# NewBoarad.net
KiCad netlist of a schematic drawn in Altium Designer
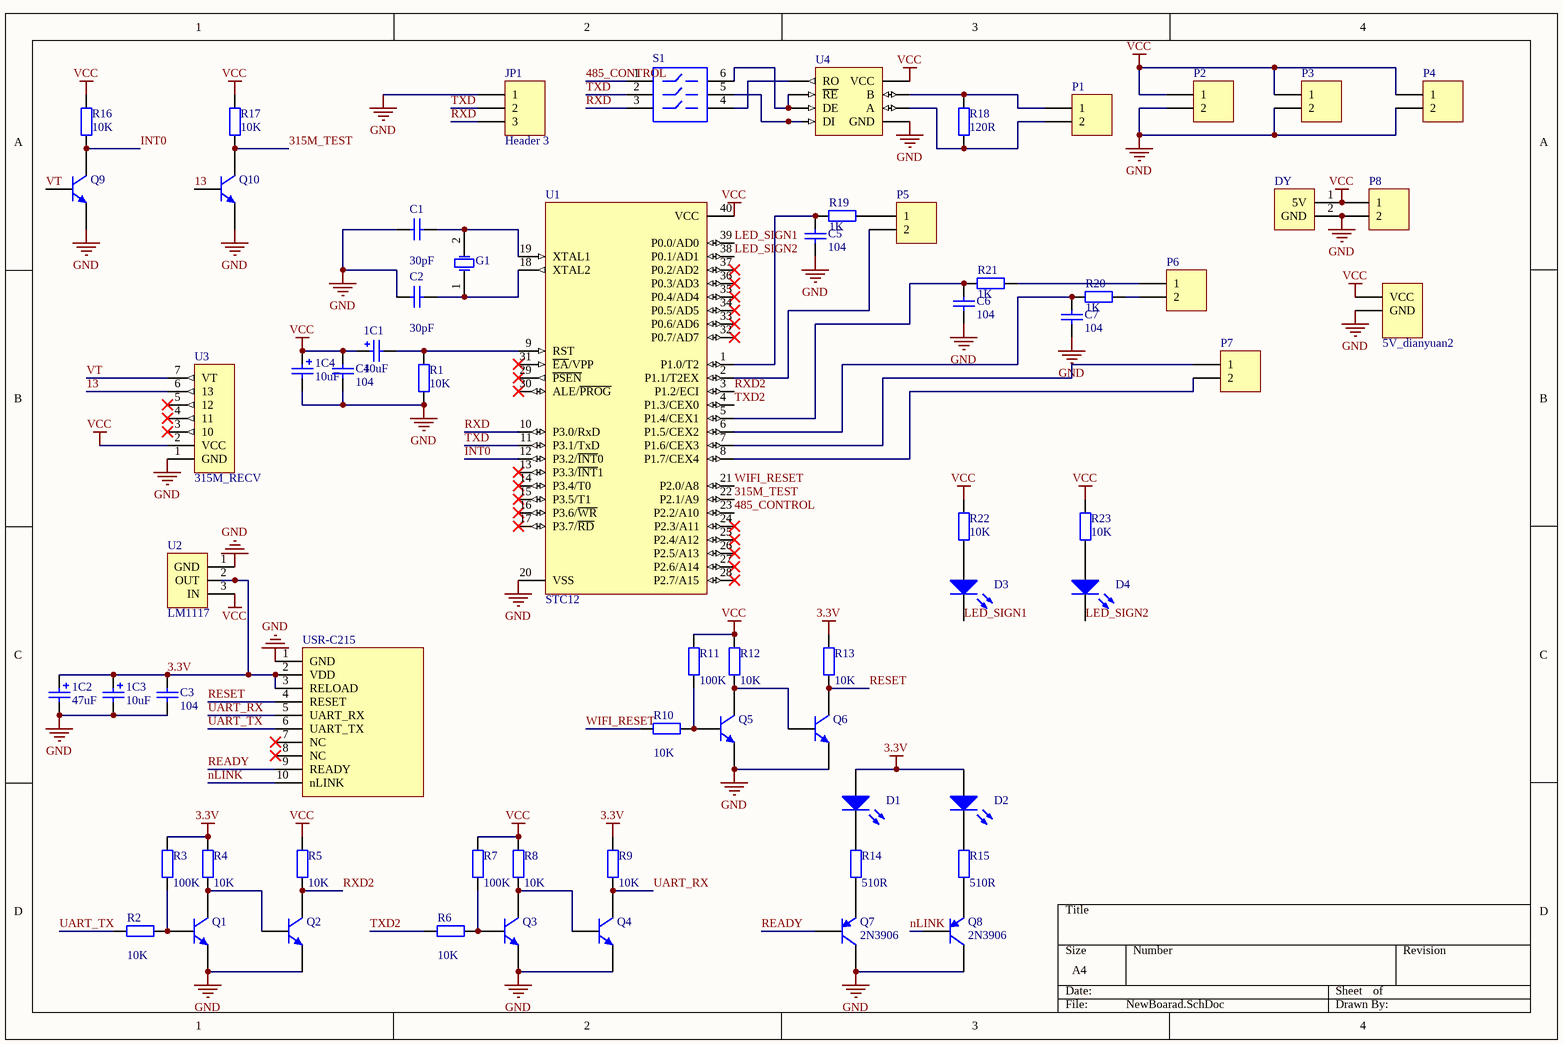
[diagram p0: NewBoarad.SchDoc]

(export (version "E")
  (design (tool "Eeschema 10.0.6"))
  (components
    (comp (ref "1C1")
      (value "10uF")
      (footprint "CAPPR5-5X5")
      (description "Polarized Capacitor (Radial)")
      (fields (field (name "Comment") "Cap Pol1") (field (name "PUBLISHER") "Altium Limited"))
      (libsource (lib "Miscellaneous Devices") (part "Cap Pol1"))
    )
    (comp (ref "1C2")
      (value "47uF")
      (footprint "CAPPR5-5X5")
      (description "Polarized Capacitor (Radial)")
      (fields (field (name "Comment") "Cap Pol1") (field (name "PUBLISHER") "Altium Limited"))
      (libsource (lib "Miscellaneous Devices") (part "Cap Pol1"))
    )
    (comp (ref "1C3")
      (value "10uF")
      (footprint "CAPPR5-5X5")
      (description "Polarized Capacitor (Radial)")
      (fields (field (name "Comment") "Cap Pol1") (field (name "PUBLISHER") "Altium Limited"))
      (libsource (lib "Miscellaneous Devices") (part "Cap Pol1"))
    )
    (comp (ref "1C4")
      (value "10uF")
      (footprint "CAPPR5-5X5")
      (description "Polarized Capacitor (Radial)")
      (fields (field (name "Comment") "Cap Pol1") (field (name "PUBLISHER") "Altium Limited"))
      (libsource (lib "Miscellaneous Devices") (part "Cap Pol1"))
    )
    (comp (ref "5V_dianyuan2")
      (value "5V_dianyuan2")
      (footprint "5v_dianyuan2")
      (libsource (lib "*") (part "5V_dianyuan2"))
    )
    (comp (ref "C1")
      (value "30pF")
      (footprint "CAPR5.08-7.8X3.2")
      (description "Capacitor")
      (fields (field (name "PUBLISHER") "Altium Limited"))
      (libsource (lib "Miscellaneous Devices") (part "Cap"))
    )
    (comp (ref "C2")
      (value "30pF")
      (footprint "CAPR5.08-7.8X3.2")
      (description "Capacitor")
      (fields (field (name "Comment") "104") (field (name "PUBLISHER") "Altium Limited"))
      (libsource (lib "Miscellaneous Devices") (part "Cap"))
    )
    (comp (ref "C3")
      (value "104")
      (footprint "CAPR5.08-7.8X3.2")
      (description "Capacitor")
      (fields (field (name "PUBLISHER") "Altium Limited"))
      (libsource (lib "Miscellaneous Devices") (part "Cap"))
    )
    (comp (ref "C4")
      (value "104")
      (footprint "CAPR5.08-7.8X3.2")
      (description "Capacitor")
      (fields (field (name "PUBLISHER") "Altium Limited"))
      (libsource (lib "Miscellaneous Devices") (part "Cap"))
    )
    (comp (ref "C5")
      (value "104")
      (footprint "CAPR5.08-7.8X3.2")
      (description "Capacitor")
      (fields (field (name "PUBLISHER") "Altium Limited"))
      (libsource (lib "Miscellaneous Devices") (part "Cap"))
    )
    (comp (ref "C6")
      (value "104")
      (footprint "CAPR5.08-7.8X3.2")
      (description "Capacitor")
      (fields (field (name "PUBLISHER") "Altium Limited"))
      (libsource (lib "Miscellaneous Devices") (part "Cap"))
    )
    (comp (ref "C7")
      (value "104")
      (footprint "CAPR5.08-7.8X3.2")
      (description "Capacitor")
      (fields (field (name "PUBLISHER") "Altium Limited"))
      (libsource (lib "Miscellaneous Devices") (part "Cap"))
    )
    (comp (ref "D1")
      (value "LED0")
      (footprint "LED-0")
      (description "Typical INFRARED GaAs LED")
      (fields (field (name "PUBLISHER") "Altium Limited"))
      (libsource (lib "*") (part "LED0"))
    )
    (comp (ref "D2")
      (value "LED0")
      (footprint "LED-0")
      (description "Typical INFRARED GaAs LED")
      (fields (field (name "PUBLISHER") "Altium Limited"))
      (libsource (lib "*") (part "LED0"))
    )
    (comp (ref "D3")
      (value "LED0")
      (footprint "LED-0")
      (description "Typical INFRARED GaAs LED")
      (fields (field (name "PUBLISHER") "Altium Limited"))
      (libsource (lib "*") (part "LED0"))
    )
    (comp (ref "D4")
      (value "LED0")
      (footprint "LED-0")
      (description "Typical INFRARED GaAs LED")
      (fields (field (name "PUBLISHER") "Altium Limited"))
      (libsource (lib "*") (part "LED0"))
    )
    (comp (ref "DY")
      (value "5V_yuankong")
      (footprint "5V_yuankong")
      (libsource (lib "HWL_1") (part "5V_yuankong"))
    )
    (comp (ref "G1")
      (value "XTAL")
      (footprint "CAPR5.08-7.8X3.2")
      (description "Crystal Oscillator")
      (fields (field (name "PUBLISHER") "Altium Limited"))
      (libsource (lib "Miscellaneous Devices") (part "XTAL"))
    )
    (comp (ref "JP1")
      (value "Header 3")
      (footprint "HDR1X3")
      (description "Header, 3-Pin")
      (fields (field (name "PUBLISHER") "Altium Limited"))
      (libsource (lib "Miscellaneous Connectors") (part "Header 3"))
    )
    (comp (ref "P1")
      (value "duanzi-2")
      (footprint "duanzi-2")
      (description "Header, 2-Pin")
      (fields (field (name "PUBLISHER") "Altium Limited"))
      (libsource (lib "*") (part "duanzi-2"))
    )
    (comp (ref "P2")
      (value "duanzi-2")
      (footprint "duanzi-2")
      (description "Header, 2-Pin")
      (fields (field (name "PUBLISHER") "Altium Limited"))
      (libsource (lib "*") (part "duanzi-2"))
    )
    (comp (ref "P3")
      (value "duanzi-2")
      (footprint "duanzi-2")
      (description "Header, 2-Pin")
      (fields (field (name "PUBLISHER") "Altium Limited"))
      (libsource (lib "*") (part "duanzi-2"))
    )
    (comp (ref "P4")
      (value "duanzi-2")
      (footprint "duanzi-2")
      (description "Header, 2-Pin")
      (fields (field (name "PUBLISHER") "Altium Limited"))
      (libsource (lib "*") (part "duanzi-2"))
    )
    (comp (ref "P5")
      (value "duanzi-2")
      (footprint "duanzi-2")
      (description "Header, 2-Pin")
      (fields (field (name "PUBLISHER") "Altium Limited"))
      (libsource (lib "*") (part "duanzi-2"))
    )
    (comp (ref "P6")
      (value "duanzi-2")
      (footprint "duanzi-2")
      (description "Header, 2-Pin")
      (fields (field (name "PUBLISHER") "Altium Limited"))
      (libsource (lib "*") (part "duanzi-2"))
    )
    (comp (ref "P7")
      (value "duanzi-2")
      (footprint "duanzi-2")
      (description "Header, 2-Pin")
      (fields (field (name "PUBLISHER") "Altium Limited"))
      (libsource (lib "*") (part "duanzi-2"))
    )
    (comp (ref "P8")
      (value "duanzi-2")
      (footprint "duanzi-2")
      (description "Header, 2-Pin")
      (fields (field (name "PUBLISHER") "Altium Limited"))
      (libsource (lib "*") (part "duanzi-2"))
    )
    (comp (ref "Q1")
      (value "2N3904")
      (footprint "TO-92A")
      (description "NPN General Purpose Amplifier")
      (fields (field (name "PUBLISHER") "Altium Limited"))
      (libsource (lib "test") (part "2N3904"))
    )
    (comp (ref "Q2")
      (value "2N3904")
      (footprint "TO-92A")
      (description "NPN General Purpose Amplifier")
      (fields (field (name "PUBLISHER") "Altium Limited"))
      (libsource (lib "test") (part "2N3904"))
    )
    (comp (ref "Q3")
      (value "2N3904")
      (footprint "TO-92A")
      (description "NPN General Purpose Amplifier")
      (fields (field (name "PUBLISHER") "Altium Limited"))
      (libsource (lib "test") (part "2N3904"))
    )
    (comp (ref "Q4")
      (value "2N3904")
      (footprint "TO-92A")
      (description "NPN General Purpose Amplifier")
      (fields (field (name "PUBLISHER") "Altium Limited"))
      (libsource (lib "test") (part "2N3904"))
    )
    (comp (ref "Q5")
      (value "2N3904")
      (footprint "TO-92A")
      (description "NPN General Purpose Amplifier")
      (fields (field (name "PUBLISHER") "Altium Limited"))
      (libsource (lib "test") (part "2N3904"))
    )
    (comp (ref "Q6")
      (value "2N3904")
      (footprint "TO-92A")
      (description "NPN General Purpose Amplifier")
      (fields (field (name "PUBLISHER") "Altium Limited"))
      (libsource (lib "test") (part "2N3904"))
    )
    (comp (ref "Q7")
      (value "2N3906")
      (footprint "TO-92A")
      (description "PNP General Purpose Amplifier")
      (fields (field (name "PUBLISHER") "Altium Limited"))
      (libsource (lib "test") (part "2N3906"))
    )
    (comp (ref "Q8")
      (value "2N3906")
      (footprint "TO-92A")
      (description "PNP General Purpose Amplifier")
      (fields (field (name "PUBLISHER") "Altium Limited"))
      (libsource (lib "test") (part "2N3906"))
    )
    (comp (ref "Q9")
      (value "2N3904")
      (footprint "TO-92A")
      (description "NPN General Purpose Amplifier")
      (fields (field (name "PUBLISHER") "Altium Limited"))
      (libsource (lib "test") (part "2N3904"))
    )
    (comp (ref "Q10")
      (value "2N3904")
      (footprint "TO-92A")
      (description "NPN General Purpose Amplifier")
      (fields (field (name "PUBLISHER") "Altium Limited"))
      (libsource (lib "test") (part "2N3904"))
    )
    (comp (ref "R1")
      (value "10K")
      (footprint "AXIAL-0.3")
      (description "Resistor")
      (fields (field (name "PUBLISHER") "Altium Limited"))
      (libsource (lib "") (part "Res2_1"))
    )
    (comp (ref "R2")
      (value "10K")
      (footprint "AXIAL-0.3")
      (description "Resistor")
      (fields (field (name "Comment") "1K") (field (name "PUBLISHER") "Altium Limited"))
      (libsource (lib "Miscellaneous Devices") (part "Res2"))
    )
    (comp (ref "R3")
      (value "100K")
      (footprint "AXIAL-0.3")
      (description "Resistor")
      (fields (field (name "Comment") "1K") (field (name "PUBLISHER") "Altium Limited"))
      (libsource (lib "") (part "Res2_1"))
    )
    (comp (ref "R4")
      (value "10K")
      (footprint "AXIAL-0.3")
      (description "Resistor")
      (fields (field (name "Comment") "1K") (field (name "PUBLISHER") "Altium Limited"))
      (libsource (lib "") (part "Res2_1"))
    )
    (comp (ref "R5")
      (value "10K")
      (footprint "AXIAL-0.3")
      (description "Resistor")
      (fields (field (name "Comment") "1K") (field (name "PUBLISHER") "Altium Limited"))
      (libsource (lib "") (part "Res2_1"))
    )
    (comp (ref "R6")
      (value "10K")
      (footprint "AXIAL-0.3")
      (description "Resistor")
      (fields (field (name "Comment") "1K") (field (name "PUBLISHER") "Altium Limited"))
      (libsource (lib "Miscellaneous Devices") (part "Res2"))
    )
    (comp (ref "R7")
      (value "100K")
      (footprint "AXIAL-0.3")
      (description "Resistor")
      (fields (field (name "Comment") "1K") (field (name "PUBLISHER") "Altium Limited"))
      (libsource (lib "") (part "Res2_1"))
    )
    (comp (ref "R8")
      (value "10K")
      (footprint "AXIAL-0.3")
      (description "Resistor")
      (fields (field (name "Comment") "1K") (field (name "PUBLISHER") "Altium Limited"))
      (libsource (lib "") (part "Res2_1"))
    )
    (comp (ref "R9")
      (value "10K")
      (footprint "AXIAL-0.3")
      (description "Resistor")
      (fields (field (name "Comment") "1K") (field (name "PUBLISHER") "Altium Limited"))
      (libsource (lib "") (part "Res2_1"))
    )
    (comp (ref "R10")
      (value "10K")
      (footprint "AXIAL-0.3")
      (description "Resistor")
      (fields (field (name "Comment") "1K") (field (name "PUBLISHER") "Altium Limited"))
      (libsource (lib "Miscellaneous Devices") (part "Res2"))
    )
    (comp (ref "R11")
      (value "100K")
      (footprint "AXIAL-0.3")
      (description "Resistor")
      (fields (field (name "Comment") "1K") (field (name "PUBLISHER") "Altium Limited"))
      (libsource (lib "") (part "Res2_1"))
    )
    (comp (ref "R12")
      (value "10K")
      (footprint "AXIAL-0.3")
      (description "Resistor")
      (fields (field (name "Comment") "1K") (field (name "PUBLISHER") "Altium Limited"))
      (libsource (lib "") (part "Res2_1"))
    )
    (comp (ref "R13")
      (value "10K")
      (footprint "AXIAL-0.3")
      (description "Resistor")
      (fields (field (name "Comment") "1K") (field (name "PUBLISHER") "Altium Limited"))
      (libsource (lib "") (part "Res2_1"))
    )
    (comp (ref "R14")
      (value "510R")
      (footprint "AXIAL-0.3")
      (description "Resistor")
      (fields (field (name "Comment") "1K") (field (name "PUBLISHER") "Altium Limited"))
      (libsource (lib "") (part "Res2_1"))
    )
    (comp (ref "R15")
      (value "510R")
      (footprint "AXIAL-0.3")
      (description "Resistor")
      (fields (field (name "Comment") "1K") (field (name "PUBLISHER") "Altium Limited"))
      (libsource (lib "") (part "Res2_1"))
    )
    (comp (ref "R16")
      (value "10K")
      (footprint "AXIAL-0.3")
      (description "Resistor")
      (fields (field (name "PUBLISHER") "Altium Limited"))
      (libsource (lib "") (part "Res2_1"))
    )
    (comp (ref "R17")
      (value "10K")
      (footprint "AXIAL-0.3")
      (description "Resistor")
      (fields (field (name "PUBLISHER") "Altium Limited"))
      (libsource (lib "") (part "Res2_1"))
    )
    (comp (ref "R18")
      (value "120R")
      (footprint "AXIAL-0.3")
      (description "Resistor")
      (fields (field (name "PUBLISHER") "Altium Limited"))
      (libsource (lib "") (part "Res2_1"))
    )
    (comp (ref "R19")
      (value "1K")
      (footprint "AXIAL-0.3")
      (description "Resistor")
      (fields (field (name "PUBLISHER") "Altium Limited"))
      (libsource (lib "Miscellaneous Devices") (part "Res2"))
    )
    (comp (ref "R20")
      (value "1K")
      (footprint "AXIAL-0.3")
      (description "Resistor")
      (fields (field (name "PUBLISHER") "Altium Limited"))
      (libsource (lib "Miscellaneous Devices") (part "Res2"))
    )
    (comp (ref "R21")
      (value "1K")
      (footprint "AXIAL-0.3")
      (description "Resistor")
      (fields (field (name "PUBLISHER") "Altium Limited"))
      (libsource (lib "Miscellaneous Devices") (part "Res2"))
    )
    (comp (ref "R22")
      (value "10K")
      (footprint "AXIAL-0.3")
      (description "Resistor")
      (fields (field (name "PUBLISHER") "Altium Limited"))
      (libsource (lib "") (part "Res2_1"))
    )
    (comp (ref "R23")
      (value "10K")
      (footprint "AXIAL-0.3")
      (description "Resistor")
      (fields (field (name "PUBLISHER") "Altium Limited"))
      (libsource (lib "") (part "Res2_1"))
    )
    (comp (ref "S1")
      (value "boma-3")
      (footprint "boma-3")
      (description "DIP Switch")
      (fields (field (name "PUBLISHER") "Altium Limited"))
      (libsource (lib "*") (part "boma-3"))
    )
    (comp (ref "U1")
      (value "STC12")
      (footprint "SOT129-1")
      (description "80C51 8-Bit Flash Microcontroller Family, 64 kB ISP/IAP Flash with 1 kB RAM.")
      (fields (field (name "PUBLISHER") "Altium Limited"))
      (libsource (lib "Philips Microcontroller 8-Bit") (part "P89C51RD2BN/01"))
    )
    (comp (ref "U2") (value "LM1117") (footprint "LM1117") (libsource (lib "HWL_1") (part "LM1117")))
    (comp (ref "U3")
      (value "315M_RECV")
      (footprint "315M_RECV")
      (fields (field (name "PUBLISHER") "Altium Limited"))
      (libsource (lib "*") (part "315M_RECV"))
    )
    (comp (ref "U4")
      (value "485_test")
      (footprint "485_test")
      (description "Header, 4-Pin, Dual row")
      (fields (field (name "PUBLISHER") "Altium Limited"))
      (libsource (lib "*") (part "485_test"))
    )
    (comp (ref "USR-C215")
      (value "USR-C215")
      (footprint "USR-C215-PCB封装:DIP2.0*1-10-M")
      (fields (field (name "PUBLISHER") "*"))
      (libsource (lib "*") (part "USR-C215"))
    )
  )
  (nets
    (net (code "1") (name "/13") (class "Default")
      (node (ref "Q10") (pin "2") (pinfunction "B_2") (pintype "passive"))
      (node (ref "U3") (pin "6") (pinfunction "13_6") (pintype "output"))
    )
    (net (code "2") (name "/315M_TEST") (class "Default")
      (node (ref "Q10") (pin "3") (pinfunction "C_3") (pintype "passive"))
      (node (ref "R17") (pin "2") (pinfunction "2_2") (pintype "passive"))
      (node (ref "U1") (pin "22") (pinfunction "P2.1/A9_22") (pintype "bidirectional"))
    )
    (net (code "3") (name "/485_CONTROL") (class "Default")
      (node (ref "S1") (pin "1") (pinfunction "1_1") (pintype "passive"))
      (node (ref "U1") (pin "23") (pinfunction "P2.2/A10_23") (pintype "bidirectional"))
    )
    (net (code "4") (name "/INT0") (class "Default")
      (node (ref "Q9") (pin "3") (pinfunction "C_3") (pintype "passive"))
      (node (ref "R16") (pin "2") (pinfunction "2_2") (pintype "passive"))
      (node (ref "U1") (pin "12") (pinfunction "P3.2/~{INT}0_12") (pintype "bidirectional"))
    )
    (net (code "5") (name "/LED_SIGN1") (class "Default")
      (node (ref "D3") (pin "2") (pinfunction "K_2") (pintype "passive"))
      (node (ref "U1") (pin "39") (pinfunction "P0.0/AD0_39") (pintype "bidirectional"))
    )
    (net (code "6") (name "/LED_SIGN2") (class "Default")
      (node (ref "D4") (pin "2") (pinfunction "K_2") (pintype "passive"))
      (node (ref "U1") (pin "38") (pinfunction "P0.1/AD1_38") (pintype "bidirectional"))
    )
    (net (code "7") (name "/READY") (class "Default")
      (node (ref "Q7") (pin "2") (pinfunction "B_2") (pintype "passive"))
      (node (ref "USR-C215") (pin "9") (pinfunction "READY_9") (pintype "passive"))
    )
    (net (code "8") (name "/RESET") (class "Default")
      (node (ref "Q6") (pin "3") (pinfunction "C_3") (pintype "passive"))
      (node (ref "R13") (pin "2") (pinfunction "2_2") (pintype "passive"))
      (node (ref "USR-C215") (pin "4") (pinfunction "RESET_4") (pintype "passive"))
    )
    (net (code "9") (name "/RXD") (class "Default")
      (node (ref "JP1") (pin "3") (pinfunction "3_3") (pintype "passive"))
      (node (ref "S1") (pin "3") (pinfunction "3_3") (pintype "passive"))
      (node (ref "U1") (pin "10") (pinfunction "P3.0/RxD_10") (pintype "bidirectional"))
    )
    (net (code "10") (name "/RXD2") (class "Default")
      (node (ref "Q2") (pin "3") (pinfunction "C_3") (pintype "passive"))
      (node (ref "R5") (pin "2") (pinfunction "2_2") (pintype "passive"))
      (node (ref "U1") (pin "3") (pinfunction "P1.2/ECI_3") (pintype "bidirectional"))
    )
    (net (code "11") (name "/TXD") (class "Default")
      (node (ref "JP1") (pin "2") (pinfunction "2_2") (pintype "passive"))
      (node (ref "S1") (pin "2") (pinfunction "2_2") (pintype "passive"))
      (node (ref "U1") (pin "11") (pinfunction "P3.1/TxD_11") (pintype "bidirectional"))
    )
    (net (code "12") (name "/TXD2") (class "Default")
      (node (ref "R6") (pin "1") (pinfunction "1_1") (pintype "passive"))
      (node (ref "U1") (pin "4") (pinfunction "P1.3/CEX0_4") (pintype "bidirectional"))
    )
    (net (code "13") (name "/UART_RX") (class "Default")
      (node (ref "Q4") (pin "3") (pinfunction "C_3") (pintype "passive"))
      (node (ref "R9") (pin "2") (pinfunction "2_2") (pintype "passive"))
      (node (ref "USR-C215") (pin "5") (pinfunction "UART_RX_5") (pintype "passive"))
    )
    (net (code "14") (name "/UART_TX") (class "Default")
      (node (ref "R2") (pin "1") (pinfunction "1_1") (pintype "passive"))
      (node (ref "USR-C215") (pin "6") (pinfunction "UART_TX_6") (pintype "passive"))
    )
    (net (code "15") (name "/VT") (class "Default")
      (node (ref "Q9") (pin "2") (pinfunction "B_2") (pintype "passive"))
      (node (ref "U3") (pin "7") (pinfunction "VT_7") (pintype "output"))
    )
    (net (code "16") (name "/WIFI_RESET") (class "Default")
      (node (ref "R10") (pin "1") (pinfunction "1_1") (pintype "passive"))
      (node (ref "U1") (pin "21") (pinfunction "P2.0/A8_21") (pintype "bidirectional"))
    )
    (net (code "17") (name "/nLINK") (class "Default")
      (node (ref "Q8") (pin "2") (pinfunction "B_2") (pintype "passive"))
      (node (ref "USR-C215") (pin "10") (pinfunction "nLINK_10") (pintype "passive"))
    )
    (net (code "18") (name "3.3V") (class "Default")
      (node (ref "1C2") (pin "1") (pinfunction "1_1") (pintype "passive"))
      (node (ref "1C3") (pin "1") (pinfunction "1_1") (pintype "passive"))
      (node (ref "C3") (pin "1") (pinfunction "1_1") (pintype "passive"))
      (node (ref "D1") (pin "1") (pinfunction "A_1") (pintype "passive"))
      (node (ref "D2") (pin "1") (pinfunction "A_1") (pintype "passive"))
      (node (ref "R13") (pin "1") (pinfunction "1_1") (pintype "passive"))
      (node (ref "R3") (pin "1") (pinfunction "1_1") (pintype "passive"))
      (node (ref "R4") (pin "1") (pinfunction "1_1") (pintype "passive"))
      (node (ref "R9") (pin "1") (pinfunction "1_1") (pintype "passive"))
      (node (ref "U2") (pin "2") (pinfunction "OUT_2") (pintype "passive"))
      (node (ref "USR-C215") (pin "2") (pinfunction "VDD_2") (pintype "passive"))
      (node (ref "USR-C215") (pin "3") (pinfunction "RELOAD_3") (pintype "passive"))
    )
    (net (code "19") (name "GND") (class "Default")
      (node (ref "1C2") (pin "2") (pinfunction "2_2") (pintype "passive"))
      (node (ref "1C3") (pin "2") (pinfunction "2_2") (pintype "passive"))
      (node (ref "1C4") (pin "2") (pinfunction "2_2") (pintype "passive"))
      (node (ref "5V_dianyuan2") (pin "2") (pinfunction "GND_2") (pintype "passive"))
      (node (ref "C1") (pin "1") (pinfunction "1_1") (pintype "passive"))
      (node (ref "C2") (pin "1") (pinfunction "1_1") (pintype "passive"))
      (node (ref "C3") (pin "2") (pinfunction "2_2") (pintype "passive"))
      (node (ref "C4") (pin "2") (pinfunction "2_2") (pintype "passive"))
      (node (ref "C5") (pin "2") (pinfunction "2_2") (pintype "passive"))
      (node (ref "C6") (pin "2") (pinfunction "2_2") (pintype "passive"))
      (node (ref "C7") (pin "2") (pinfunction "2_2") (pintype "passive"))
      (node (ref "DY") (pin "2") (pinfunction "GND_2") (pintype "passive"))
      (node (ref "JP1") (pin "1") (pinfunction "1_1") (pintype "passive"))
      (node (ref "P2") (pin "2") (pinfunction "2_2") (pintype "passive"))
      (node (ref "P3") (pin "2") (pinfunction "2_2") (pintype "passive"))
      (node (ref "P4") (pin "2") (pinfunction "2_2") (pintype "passive"))
      (node (ref "P8") (pin "2") (pinfunction "2_2") (pintype "passive"))
      (node (ref "Q1") (pin "1") (pinfunction "E_1") (pintype "passive"))
      (node (ref "Q10") (pin "1") (pinfunction "E_1") (pintype "passive"))
      (node (ref "Q2") (pin "1") (pinfunction "E_1") (pintype "passive"))
      (node (ref "Q3") (pin "1") (pinfunction "E_1") (pintype "passive"))
      (node (ref "Q4") (pin "1") (pinfunction "E_1") (pintype "passive"))
      (node (ref "Q5") (pin "1") (pinfunction "E_1") (pintype "passive"))
      (node (ref "Q6") (pin "1") (pinfunction "E_1") (pintype "passive"))
      (node (ref "Q7") (pin "3") (pinfunction "C_3") (pintype "passive"))
      (node (ref "Q8") (pin "3") (pinfunction "C_3") (pintype "passive"))
      (node (ref "Q9") (pin "1") (pinfunction "E_1") (pintype "passive"))
      (node (ref "R1") (pin "2") (pinfunction "2_2") (pintype "passive"))
      (node (ref "U1") (pin "20") (pinfunction "VSS_20") (pintype "power_in"))
      (node (ref "U2") (pin "1") (pinfunction "GND_1") (pintype "passive"))
      (node (ref "U3") (pin "1") (pinfunction "GND_1") (pintype "power_in"))
      (node (ref "U3") (pin "12") (pinfunction "GND_12") (pintype "power_in"))
      (node (ref "U4") (pin "5") (pinfunction "GND_5") (pintype "power_in"))
      (node (ref "USR-C215") (pin "1") (pinfunction "GND_1") (pintype "passive"))
    )
    (net (code "20") (name "Net-(D1-K)") (class "Default")
      (node (ref "D1") (pin "2") (pinfunction "K_2") (pintype "passive"))
      (node (ref "R14") (pin "1") (pinfunction "1_1") (pintype "passive"))
    )
    (net (code "21") (name "Net-(D2-K)") (class "Default")
      (node (ref "D2") (pin "2") (pinfunction "K_2") (pintype "passive"))
      (node (ref "R15") (pin "1") (pinfunction "1_1") (pintype "passive"))
    )
    (net (code "22") (name "Net-(D3-A)") (class "Default")
      (node (ref "D3") (pin "1") (pinfunction "A_1") (pintype "passive"))
      (node (ref "R22") (pin "2") (pinfunction "2_2") (pintype "passive"))
    )
    (net (code "23") (name "Net-(D4-A)") (class "Default")
      (node (ref "D4") (pin "1") (pinfunction "A_1") (pintype "passive"))
      (node (ref "R23") (pin "2") (pinfunction "2_2") (pintype "passive"))
    )
    (net (code "24") (name "Net-(G1-OSC1)") (class "Default")
      (node (ref "C2") (pin "2") (pinfunction "2_2") (pintype "passive"))
      (node (ref "G1") (pin "1") (pinfunction "OSC1_1") (pintype "passive"))
      (node (ref "U1") (pin "18") (pinfunction "XTAL2_18") (pintype "output"))
    )
    (net (code "25") (name "Net-(G1-OSC2)") (class "Default")
      (node (ref "C1") (pin "2") (pinfunction "2_2") (pintype "passive"))
      (node (ref "G1") (pin "2") (pinfunction "OSC2_2") (pintype "passive"))
      (node (ref "U1") (pin "19") (pinfunction "XTAL1_19") (pintype "input"))
    )
    (net (code "26") (name "Net-(P5-Pad1)") (class "Default")
      (node (ref "P5") (pin "1") (pinfunction "1_1") (pintype "passive"))
      (node (ref "R19") (pin "2") (pinfunction "2_2") (pintype "passive"))
    )
    (net (code "27") (name "Net-(P6-Pad1)") (class "Default")
      (node (ref "P6") (pin "1") (pinfunction "1_1") (pintype "passive"))
      (node (ref "R21") (pin "2") (pinfunction "2_2") (pintype "passive"))
    )
    (net (code "28") (name "Net-(P6-Pad2)") (class "Default")
      (node (ref "P6") (pin "2") (pinfunction "2_2") (pintype "passive"))
      (node (ref "R20") (pin "2") (pinfunction "2_2") (pintype "passive"))
    )
    (net (code "29") (name "Net-(Q1-B)") (class "Default")
      (node (ref "Q1") (pin "2") (pinfunction "B_2") (pintype "passive"))
      (node (ref "R2") (pin "2") (pinfunction "2_2") (pintype "passive"))
      (node (ref "R3") (pin "2") (pinfunction "2_2") (pintype "passive"))
    )
    (net (code "30") (name "Net-(Q1-C)") (class "Default")
      (node (ref "Q1") (pin "3") (pinfunction "C_3") (pintype "passive"))
      (node (ref "Q2") (pin "2") (pinfunction "B_2") (pintype "passive"))
      (node (ref "R4") (pin "2") (pinfunction "2_2") (pintype "passive"))
    )
    (net (code "31") (name "Net-(Q3-B)") (class "Default")
      (node (ref "Q3") (pin "2") (pinfunction "B_2") (pintype "passive"))
      (node (ref "R6") (pin "2") (pinfunction "2_2") (pintype "passive"))
      (node (ref "R7") (pin "2") (pinfunction "2_2") (pintype "passive"))
    )
    (net (code "32") (name "Net-(Q3-C)") (class "Default")
      (node (ref "Q3") (pin "3") (pinfunction "C_3") (pintype "passive"))
      (node (ref "Q4") (pin "2") (pinfunction "B_2") (pintype "passive"))
      (node (ref "R8") (pin "2") (pinfunction "2_2") (pintype "passive"))
    )
    (net (code "33") (name "Net-(Q5-B)") (class "Default")
      (node (ref "Q5") (pin "2") (pinfunction "B_2") (pintype "passive"))
      (node (ref "R10") (pin "2") (pinfunction "2_2") (pintype "passive"))
      (node (ref "R11") (pin "2") (pinfunction "2_2") (pintype "passive"))
    )
    (net (code "34") (name "Net-(Q5-C)") (class "Default")
      (node (ref "Q5") (pin "3") (pinfunction "C_3") (pintype "passive"))
      (node (ref "Q6") (pin "2") (pinfunction "B_2") (pintype "passive"))
      (node (ref "R12") (pin "2") (pinfunction "2_2") (pintype "passive"))
    )
    (net (code "35") (name "Net-(Q7-E)") (class "Default")
      (node (ref "Q7") (pin "1") (pinfunction "E_1") (pintype "passive"))
      (node (ref "R14") (pin "2") (pinfunction "2_2") (pintype "passive"))
    )
    (net (code "36") (name "Net-(Q8-E)") (class "Default")
      (node (ref "Q8") (pin "1") (pinfunction "E_1") (pintype "passive"))
      (node (ref "R15") (pin "2") (pinfunction "2_2") (pintype "passive"))
    )
    (net (code "37") (name "Net-(U1-P1.0{slash}T2)") (class "Default")
      (node (ref "C5") (pin "1") (pinfunction "1_1") (pintype "passive"))
      (node (ref "R19") (pin "1") (pinfunction "1_1") (pintype "passive"))
      (node (ref "U1") (pin "1") (pinfunction "P1.0/T2_1") (pintype "bidirectional"))
    )
    (net (code "38") (name "Net-(U1-P1.1{slash}T2EX)") (class "Default")
      (node (ref "P5") (pin "2") (pinfunction "2_2") (pintype "passive"))
      (node (ref "U1") (pin "2") (pinfunction "P1.1/T2EX_2") (pintype "bidirectional"))
    )
    (net (code "39") (name "Net-(U1-P1.4{slash}CEX1)") (class "Default")
      (node (ref "C6") (pin "1") (pinfunction "1_1") (pintype "passive"))
      (node (ref "R21") (pin "1") (pinfunction "1_1") (pintype "passive"))
      (node (ref "U1") (pin "5") (pinfunction "P1.4/CEX1_5") (pintype "bidirectional"))
    )
    (net (code "40") (name "Net-(U1-P1.5{slash}CEX2)") (class "Default")
      (node (ref "C7") (pin "1") (pinfunction "1_1") (pintype "passive"))
      (node (ref "R20") (pin "1") (pinfunction "1_1") (pintype "passive"))
      (node (ref "U1") (pin "6") (pinfunction "P1.5/CEX2_6") (pintype "bidirectional"))
    )
    (net (code "41") (name "Net-(U1-P1.6{slash}CEX3)") (class "Default")
      (node (ref "P7") (pin "1") (pinfunction "1_1") (pintype "passive"))
      (node (ref "U1") (pin "7") (pinfunction "P1.6/CEX3_7") (pintype "bidirectional"))
    )
    (net (code "42") (name "Net-(U1-P1.7{slash}CEX4)") (class "Default")
      (node (ref "P7") (pin "2") (pinfunction "2_2") (pintype "passive"))
      (node (ref "U1") (pin "8") (pinfunction "P1.7/CEX4_8") (pintype "bidirectional"))
    )
    (net (code "43") (name "Net-(U1-RST)") (class "Default")
      (node (ref "1C1") (pin "2") (pinfunction "2_2") (pintype "passive"))
      (node (ref "R1") (pin "1") (pinfunction "1_1") (pintype "passive"))
      (node (ref "U1") (pin "9") (pinfunction "RST_9") (pintype "input"))
    )
    (net (code "44") (name "Net-(U4-A)") (class "Default")
      (node (ref "P1") (pin "2") (pinfunction "2_2") (pintype "passive"))
      (node (ref "R18") (pin "2") (pinfunction "2_2") (pintype "passive"))
      (node (ref "U4") (pin "6") (pinfunction "A_6") (pintype "bidirectional"))
    )
    (net (code "45") (name "Net-(U4-B)") (class "Default")
      (node (ref "P1") (pin "1") (pinfunction "1_1") (pintype "passive"))
      (node (ref "R18") (pin "1") (pinfunction "1_1") (pintype "passive"))
      (node (ref "U4") (pin "7") (pinfunction "B_7") (pintype "bidirectional"))
    )
    (net (code "46") (name "Net-(U4-DE)") (class "Default")
      (node (ref "S1") (pin "6") (pinfunction "6_6") (pintype "passive"))
      (node (ref "U4") (pin "2") (pinfunction "~{RE}_2") (pintype "input"))
      (node (ref "U4") (pin "3") (pinfunction "DE_3") (pintype "input"))
    )
    (net (code "47") (name "Net-(U4-DI)") (class "Default")
      (node (ref "S1") (pin "5") (pinfunction "5_5") (pintype "passive"))
      (node (ref "U4") (pin "4") (pinfunction "DI_4") (pintype "input"))
    )
    (net (code "48") (name "Net-(U4-RO)") (class "Default")
      (node (ref "S1") (pin "4") (pinfunction "4_4") (pintype "passive"))
      (node (ref "U4") (pin "1") (pinfunction "RO_1") (pintype "output"))
    )
    (net (code "49") (name "VCC") (class "Default")
      (node (ref "1C1") (pin "1") (pinfunction "1_1") (pintype "passive"))
      (node (ref "1C4") (pin "1") (pinfunction "1_1") (pintype "passive"))
      (node (ref "5V_dianyuan2") (pin "1") (pinfunction "VCC_1") (pintype "passive"))
      (node (ref "C4") (pin "1") (pinfunction "1_1") (pintype "passive"))
      (node (ref "DY") (pin "1") (pinfunction "5V_1") (pintype "passive"))
      (node (ref "P2") (pin "1") (pinfunction "1_1") (pintype "passive"))
      (node (ref "P3") (pin "1") (pinfunction "1_1") (pintype "passive"))
      (node (ref "P4") (pin "1") (pinfunction "1_1") (pintype "passive"))
      (node (ref "P8") (pin "1") (pinfunction "1_1") (pintype "passive"))
      (node (ref "R11") (pin "1") (pinfunction "1_1") (pintype "passive"))
      (node (ref "R12") (pin "1") (pinfunction "1_1") (pintype "passive"))
      (node (ref "R16") (pin "1") (pinfunction "1_1") (pintype "passive"))
      (node (ref "R17") (pin "1") (pinfunction "1_1") (pintype "passive"))
      (node (ref "R22") (pin "1") (pinfunction "1_1") (pintype "passive"))
      (node (ref "R23") (pin "1") (pinfunction "1_1") (pintype "passive"))
      (node (ref "R5") (pin "1") (pinfunction "1_1") (pintype "passive"))
      (node (ref "R7") (pin "1") (pinfunction "1_1") (pintype "passive"))
      (node (ref "R8") (pin "1") (pinfunction "1_1") (pintype "passive"))
      (node (ref "U1") (pin "40") (pinfunction "VCC_40") (pintype "power_in"))
      (node (ref "U2") (pin "3") (pinfunction "IN_3") (pintype "passive"))
      (node (ref "U3") (pin "13") (pinfunction "VCC_13") (pintype "power_in"))
      (node (ref "U3") (pin "2") (pinfunction "VCC_2") (pintype "power_in"))
      (node (ref "U4") (pin "8") (pinfunction "VCC_8") (pintype "power_in"))
    )
    (net (code "50") (name "unconnected-(U1-ALE{slash}~{PROG}-Pad30)") (class "Default")
      (node (ref "U1") (pin "30") (pinfunction "ALE/~{PROG}_30") (pintype "bidirectional+no_connect"))
    )
    (net (code "51") (name "unconnected-(U1-P0.2{slash}AD2-Pad37)") (class "Default")
      (node (ref "U1") (pin "37") (pinfunction "P0.2/AD2_37") (pintype "bidirectional+no_connect"))
    )
    (net (code "52") (name "unconnected-(U1-P0.3{slash}AD3-Pad36)") (class "Default")
      (node (ref "U1") (pin "36") (pinfunction "P0.3/AD3_36") (pintype "bidirectional+no_connect"))
    )
    (net (code "53") (name "unconnected-(U1-P0.4{slash}AD4-Pad35)") (class "Default")
      (node (ref "U1") (pin "35") (pinfunction "P0.4/AD4_35") (pintype "bidirectional+no_connect"))
    )
    (net (code "54") (name "unconnected-(U1-P0.5{slash}AD5-Pad34)") (class "Default")
      (node (ref "U1") (pin "34") (pinfunction "P0.5/AD5_34") (pintype "bidirectional+no_connect"))
    )
    (net (code "55") (name "unconnected-(U1-P0.6{slash}AD6-Pad33)") (class "Default")
      (node (ref "U1") (pin "33") (pinfunction "P0.6/AD6_33") (pintype "bidirectional+no_connect"))
    )
    (net (code "56") (name "unconnected-(U1-P0.7{slash}AD7-Pad32)") (class "Default")
      (node (ref "U1") (pin "32") (pinfunction "P0.7/AD7_32") (pintype "bidirectional+no_connect"))
    )
    (net (code "57") (name "unconnected-(U1-P2.3{slash}A11-Pad24)") (class "Default")
      (node (ref "U1") (pin "24") (pinfunction "P2.3/A11_24") (pintype "bidirectional+no_connect"))
    )
    (net (code "58") (name "unconnected-(U1-P2.4{slash}A12-Pad25)") (class "Default")
      (node (ref "U1") (pin "25") (pinfunction "P2.4/A12_25") (pintype "bidirectional+no_connect"))
    )
    (net (code "59") (name "unconnected-(U1-P2.5{slash}A13-Pad26)") (class "Default")
      (node (ref "U1") (pin "26") (pinfunction "P2.5/A13_26") (pintype "bidirectional+no_connect"))
    )
    (net (code "60") (name "unconnected-(U1-P2.6{slash}A14-Pad27)") (class "Default")
      (node (ref "U1") (pin "27") (pinfunction "P2.6/A14_27") (pintype "bidirectional+no_connect"))
    )
    (net (code "61") (name "unconnected-(U1-P2.7{slash}A15-Pad28)") (class "Default")
      (node (ref "U1") (pin "28") (pinfunction "P2.7/A15_28") (pintype "bidirectional+no_connect"))
    )
    (net (code "62") (name "unconnected-(U1-P3.3{slash}~{INT}1-Pad13)") (class "Default")
      (node (ref "U1") (pin "13") (pinfunction "P3.3/~{INT}1_13") (pintype "bidirectional+no_connect"))
    )
    (net (code "63") (name "unconnected-(U1-P3.4{slash}T0-Pad14)") (class "Default")
      (node (ref "U1") (pin "14") (pinfunction "P3.4/T0_14") (pintype "bidirectional+no_connect"))
    )
    (net (code "64") (name "unconnected-(U1-P3.5{slash}T1-Pad15)") (class "Default")
      (node (ref "U1") (pin "15") (pinfunction "P3.5/T1_15") (pintype "bidirectional+no_connect"))
    )
    (net (code "65") (name "unconnected-(U1-P3.6{slash}~{WR}-Pad16)") (class "Default")
      (node (ref "U1") (pin "16") (pinfunction "P3.6/~{WR}_16") (pintype "bidirectional+no_connect"))
    )
    (net (code "66") (name "unconnected-(U1-P3.7{slash}~{RD}-Pad17)") (class "Default")
      (node (ref "U1") (pin "17") (pinfunction "P3.7/~{RD}_17") (pintype "bidirectional+no_connect"))
    )
    (net (code "67") (name "unconnected-(U1-~{EA}{slash}VPP-Pad31)") (class "Default")
      (node (ref "U1") (pin "31") (pinfunction "~{EA}/VPP_31") (pintype "input+no_connect"))
    )
    (net (code "68") (name "unconnected-(U1-~{PSEN}-Pad29)") (class "Default")
      (node (ref "U1") (pin "29") (pinfunction "~{PSEN}_29") (pintype "output+no_connect"))
    )
    (net (code "69") (name "unconnected-(U3-10-Pad3)") (class "Default")
      (node (ref "U3") (pin "3") (pinfunction "10_3") (pintype "output+no_connect"))
    )
    (net (code "70") (name "unconnected-(U3-11-Pad4)") (class "Default")
      (node (ref "U3") (pin "4") (pinfunction "11_4") (pintype "output+no_connect"))
    )
    (net (code "71") (name "unconnected-(U3-12-Pad5)") (class "Default")
      (node (ref "U3") (pin "5") (pinfunction "12_5") (pintype "output+no_connect"))
    )
    (net (code "72") (name "unconnected-(USR-C215-NC-Pad7)") (class "Default")
      (node (ref "USR-C215") (pin "7") (pinfunction "NC_7") (pintype "passive+no_connect"))
    )
    (net (code "73") (name "unconnected-(USR-C215-NC-Pad8)") (class "Default")
      (node (ref "USR-C215") (pin "8") (pinfunction "NC_8") (pintype "passive+no_connect"))
    )
  )
)
